# LazuriteBLE_rev1.net
KiCad netlist of a schematic drawn in EAGLE
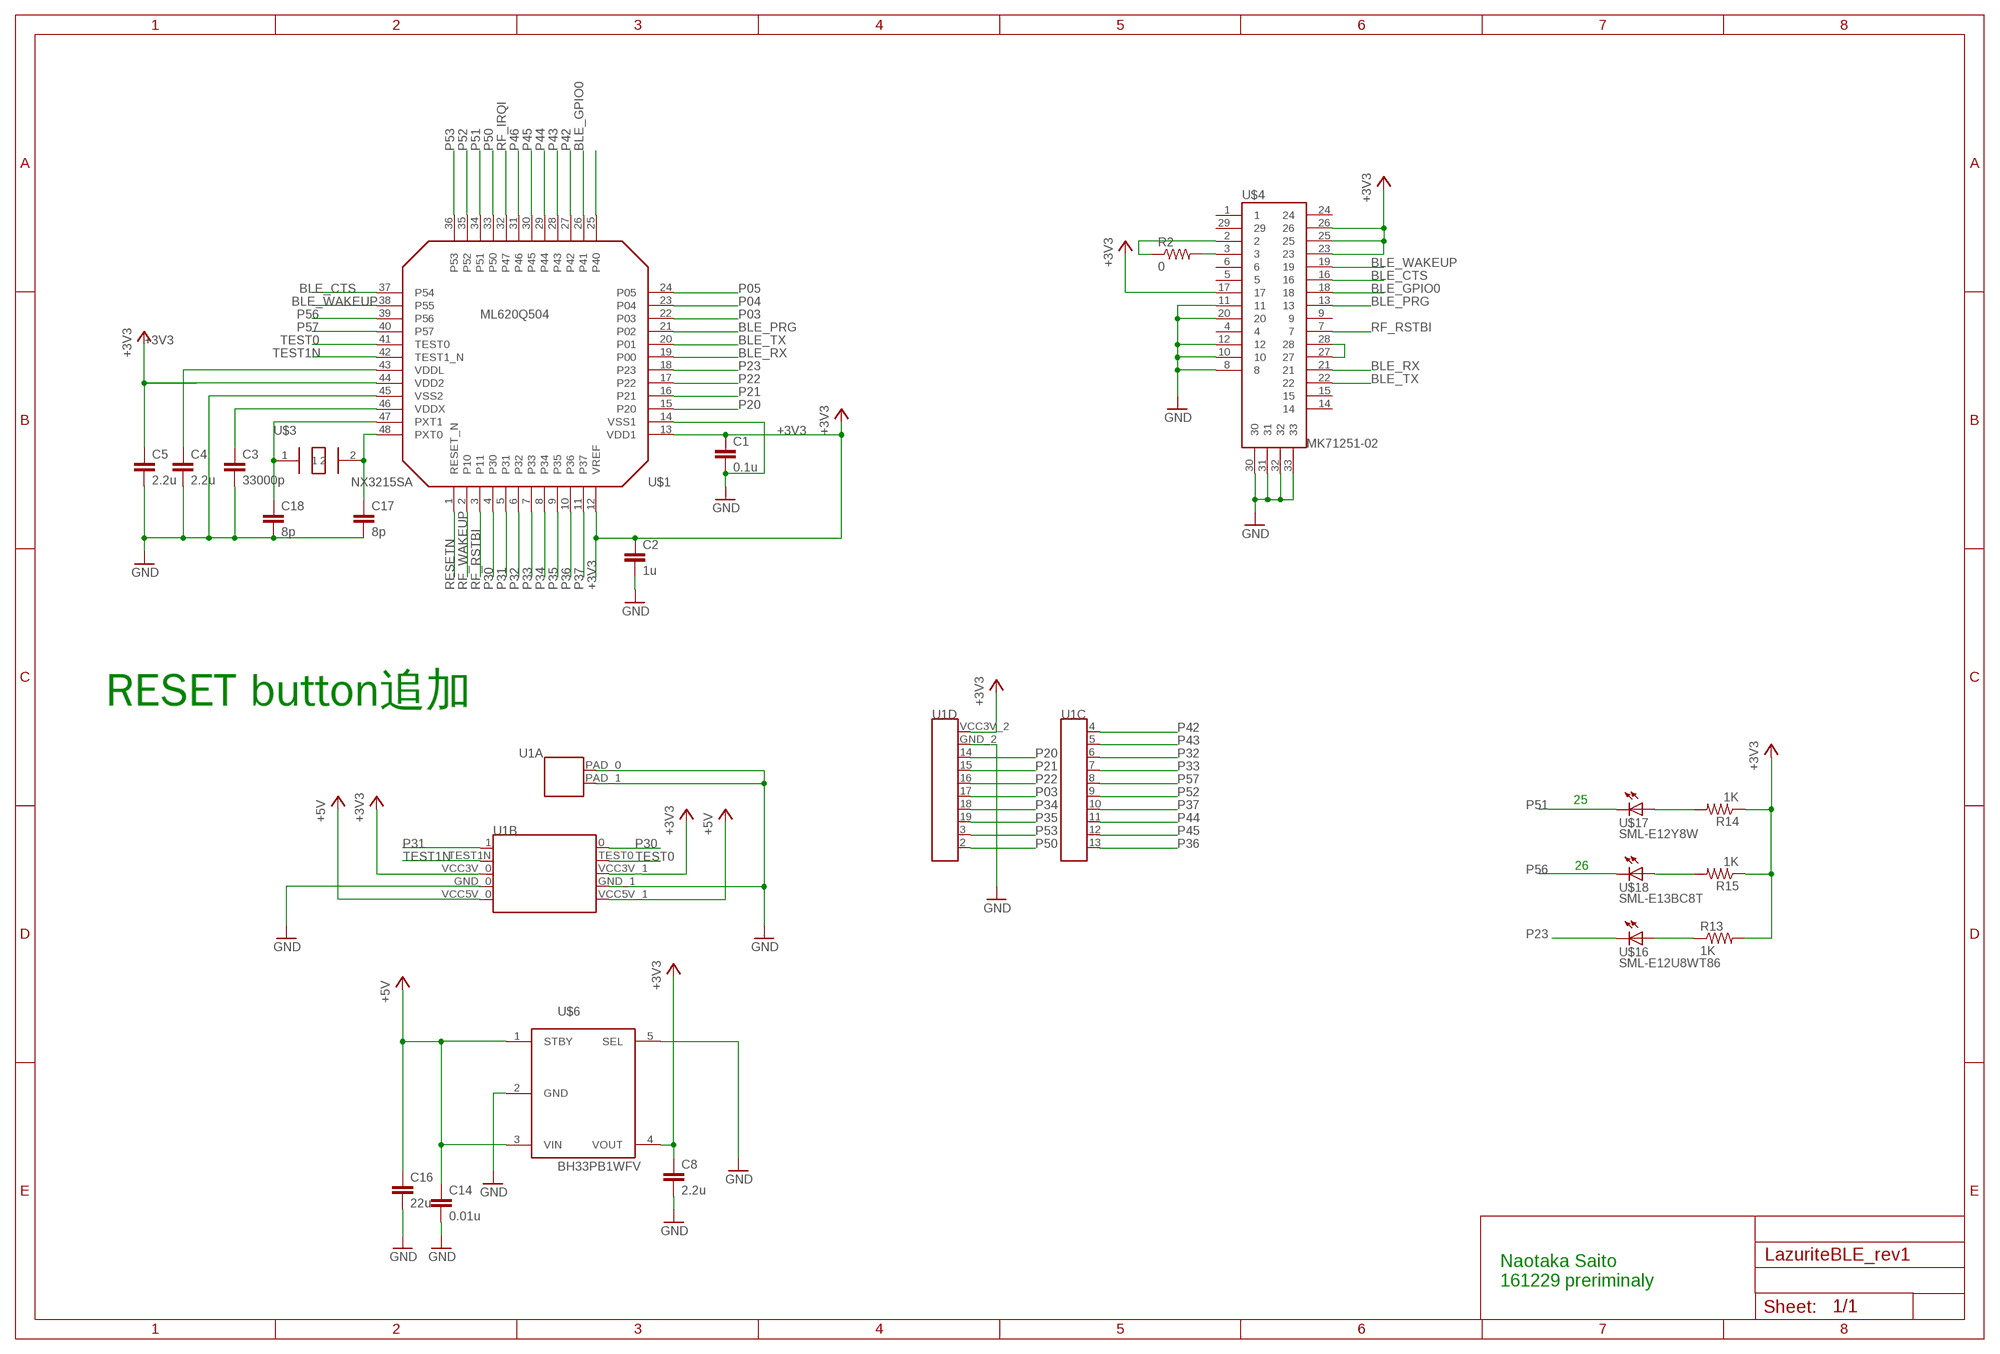
[diagram p0: schematic, sheet 1]

(export (version "E")
  (design (tool "Eeschema 10.0.6"))
  (components
    (comp (ref "C1")
      (value "0.1u")
      (footprint "eagle-import:C0402")
      (libsource (lib "eagle-import") (part "C-EUC0402"))
    )
    (comp (ref "C2")
      (value "1u")
      (footprint "eagle-import:C0402")
      (libsource (lib "eagle-import") (part "C-EUC0402"))
    )
    (comp (ref "C3")
      (value "33000p")
      (footprint "eagle-import:C0402")
      (libsource (lib "eagle-import") (part "C-EUC0402"))
    )
    (comp (ref "C4")
      (value "2.2u")
      (footprint "eagle-import:C0402")
      (libsource (lib "eagle-import") (part "C-EUC0402"))
    )
    (comp (ref "C5")
      (value "2.2u")
      (footprint "eagle-import:C0402")
      (libsource (lib "eagle-import") (part "C-EUC0402"))
    )
    (comp (ref "C8")
      (value "2.2u")
      (footprint "eagle-import:C0402")
      (libsource (lib "eagle-import") (part "C-EUC0402"))
    )
    (comp (ref "C14")
      (value "0.01u")
      (footprint "eagle-import:C0402")
      (libsource (lib "eagle-import") (part "C-EUC0402"))
    )
    (comp (ref "C16")
      (value "22u")
      (footprint "eagle-import:C1206")
      (libsource (lib "eagle-import") (part "C-EUC1206"))
    )
    (comp (ref "C17")
      (value "8p")
      (footprint "eagle-import:C0402")
      (libsource (lib "eagle-import") (part "C-EUC0402"))
    )
    (comp (ref "C18")
      (value "8p")
      (footprint "eagle-import:C0402")
      (libsource (lib "eagle-import") (part "C-EUC0402"))
    )
    (comp (ref "R2")
      (value "0")
      (footprint "eagle-import:R0402")
      (libsource (lib "eagle-import") (part "R-US_R0402"))
    )
    (comp (ref "R13")
      (value "1K")
      (footprint "eagle-import:R0402")
      (libsource (lib "eagle-import") (part "R-US_R0402"))
    )
    (comp (ref "R14")
      (value "1K")
      (footprint "eagle-import:R0402")
      (libsource (lib "eagle-import") (part "R-US_R0402"))
    )
    (comp (ref "R15")
      (value "1K")
      (footprint "eagle-import:R0402")
      (libsource (lib "eagle-import") (part "R-US_R0402"))
    )
    (comp (ref "U$1")
      (value "ML620Q504")
      (footprint "eagle-import:ML620Q504")
      (libsource (lib "eagle-import") (part "ML620Q504"))
    )
    (comp (ref "U$3")
      (value "NX3215SA")
      (footprint "eagle-import:NX3215SA-32,768K-SFD-MUA-14")
      (libsource (lib "eagle-import") (part "NX3215SA"))
    )
    (comp (ref "U$4")
      (value "MK71251-02")
      (footprint "eagle-import:MK71251-02")
      (libsource (lib "eagle-import") (part "MK71251-02"))
    )
    (comp (ref "U$6")
      (value "BH33PB1WFV")
      (footprint "eagle-import:HVSOF5")
      (libsource (lib "eagle-import") (part "BHXXPB1WFV"))
    )
    (comp (ref "U$16")
      (value "SML-E12U8WT86")
      (footprint "eagle-import:SML-E1X")
      (libsource (lib "eagle-import") (part "SML-E1X"))
    )
    (comp (ref "U$17")
      (value "SML-E12Y8W")
      (footprint "eagle-import:SML-E1X")
      (libsource (lib "eagle-import") (part "SML-E1X"))
    )
    (comp (ref "U$18")
      (value "SML-E13BC8T")
      (footprint "eagle-import:SML-E1X")
      (libsource (lib "eagle-import") (part "SML-E1X"))
    )
    (comp (ref "U1")
      (value "LAZURITE920J")
      (footprint "eagle-import:LAZURITE920J2")
      (libsource (lib "eagle-import") (part "LAZURITE920J"))
    )
  )
  (nets
    (net (code "1") (name "+3V3") (class "Default")
      (node (ref "C1") (pin "1") (pinfunction "1_1") (pintype "passive"))
      (node (ref "C2") (pin "1") (pinfunction "1_1") (pintype "passive"))
      (node (ref "C5") (pin "1") (pinfunction "1_1") (pintype "passive"))
      (node (ref "C8") (pin "1") (pinfunction "1_1") (pintype "passive"))
      (node (ref "R13") (pin "2") (pinfunction "2_2") (pintype "passive"))
      (node (ref "R14") (pin "1") (pinfunction "1_1") (pintype "passive"))
      (node (ref "R15") (pin "1") (pinfunction "1_1") (pintype "passive"))
      (node (ref "U$1") (pin "12") (pinfunction "VREF_12") (pintype "bidirectional"))
      (node (ref "U$1") (pin "13") (pinfunction "VDD1_13") (pintype "bidirectional"))
      (node (ref "U$1") (pin "44") (pinfunction "VDD2_44") (pintype "bidirectional"))
      (node (ref "U$4") (pin "17") (pinfunction "17_17") (pintype "power_in"))
      (node (ref "U$4") (pin "23") (pinfunction "23_23") (pintype "bidirectional"))
      (node (ref "U$4") (pin "25") (pinfunction "25_25") (pintype "bidirectional"))
      (node (ref "U$4") (pin "26") (pinfunction "26_26") (pintype "bidirectional"))
      (node (ref "U$6") (pin "4") (pinfunction "VOUT_4") (pintype "bidirectional"))
      (node (ref "U1") (pin "VCC3V_0") (pinfunction "VCC3V_0_VCC3V_0") (pintype "passive"))
      (node (ref "U1") (pin "VCC3V_1") (pinfunction "VCC3V_1_VCC3V_1") (pintype "passive"))
      (node (ref "U1") (pin "VCC3V_2") (pinfunction "VCC3V_2_VCC3V_2") (pintype "passive"))
    )
    (net (code "2") (name "+5V") (class "Default")
      (node (ref "C14") (pin "1") (pinfunction "1_1") (pintype "passive"))
      (node (ref "C16") (pin "1") (pinfunction "1_1") (pintype "passive"))
      (node (ref "U$6") (pin "1") (pinfunction "STBY_1") (pintype "bidirectional"))
      (node (ref "U$6") (pin "3") (pinfunction "VIN_3") (pintype "bidirectional"))
      (node (ref "U1") (pin "VCC5V_0") (pinfunction "VCC5V_0_VCC5V_0") (pintype "passive"))
      (node (ref "U1") (pin "VCC5V_1") (pinfunction "VCC5V_1_VCC5V_1") (pintype "passive"))
    )
    (net (code "3") (name "/BLE_CTS") (class "Default")
      (node (ref "U$1") (pin "37") (pinfunction "P54_37") (pintype "bidirectional"))
      (node (ref "U$4") (pin "16") (pinfunction "16_16") (pintype "bidirectional"))
    )
    (net (code "4") (name "/BLE_GPIO0") (class "Default")
      (node (ref "U$1") (pin "26") (pinfunction "P41_26") (pintype "bidirectional"))
      (node (ref "U$4") (pin "18") (pinfunction "18_18") (pintype "bidirectional"))
    )
    (net (code "5") (name "/BLE_PRG") (class "Default")
      (node (ref "U$1") (pin "21") (pinfunction "P02_21") (pintype "bidirectional"))
      (node (ref "U$4") (pin "13") (pinfunction "13_13") (pintype "bidirectional"))
    )
    (net (code "6") (name "/BLE_RX") (class "Default")
      (node (ref "U$1") (pin "19") (pinfunction "P00_19") (pintype "bidirectional"))
      (node (ref "U$4") (pin "21") (pinfunction "21_21") (pintype "bidirectional"))
    )
    (net (code "7") (name "/BLE_TX") (class "Default")
      (node (ref "U$1") (pin "20") (pinfunction "P01_20") (pintype "bidirectional"))
      (node (ref "U$4") (pin "22") (pinfunction "22_22") (pintype "bidirectional"))
    )
    (net (code "8") (name "/BLE_WAKEUP") (class "Default")
      (node (ref "U$1") (pin "38") (pinfunction "P55_38") (pintype "bidirectional"))
      (node (ref "U$4") (pin "19") (pinfunction "19_19") (pintype "input"))
    )
    (net (code "9") (name "/P03") (class "Default")
      (node (ref "U$1") (pin "22") (pinfunction "P03_22") (pintype "bidirectional"))
      (node (ref "U1") (pin "17") (pinfunction "17_17") (pintype "passive"))
    )
    (net (code "10") (name "/P04") (class "Default")
      (node (ref "U$1") (pin "23") (pinfunction "P04_23") (pintype "bidirectional"))
    )
    (net (code "11") (name "/P05") (class "Default")
      (node (ref "U$1") (pin "24") (pinfunction "P05_24") (pintype "bidirectional"))
    )
    (net (code "12") (name "/P20") (class "Default")
      (node (ref "U$1") (pin "15") (pinfunction "P20_15") (pintype "bidirectional"))
      (node (ref "U1") (pin "14") (pinfunction "14_14") (pintype "passive"))
    )
    (net (code "13") (name "/P21") (class "Default")
      (node (ref "U$1") (pin "16") (pinfunction "P21_16") (pintype "bidirectional"))
      (node (ref "U1") (pin "15") (pinfunction "15_15") (pintype "passive"))
    )
    (net (code "14") (name "/P22") (class "Default")
      (node (ref "U$1") (pin "17") (pinfunction "P22_17") (pintype "bidirectional"))
      (node (ref "U1") (pin "16") (pinfunction "16_16") (pintype "passive"))
    )
    (net (code "15") (name "/P23") (class "Default")
      (node (ref "U$1") (pin "18") (pinfunction "P23_18") (pintype "bidirectional"))
      (node (ref "U$16") (pin "C") (pinfunction "C_C") (pintype "passive"))
    )
    (net (code "16") (name "/P30") (class "Default")
      (node (ref "U$1") (pin "4") (pinfunction "P30_4") (pintype "bidirectional"))
      (node (ref "U1") (pin "0") (pinfunction "0_0") (pintype "passive"))
    )
    (net (code "17") (name "/P31") (class "Default")
      (node (ref "U$1") (pin "5") (pinfunction "P31_5") (pintype "bidirectional"))
      (node (ref "U1") (pin "1") (pinfunction "1_1") (pintype "passive"))
    )
    (net (code "18") (name "/P32") (class "Default")
      (node (ref "U$1") (pin "6") (pinfunction "P32_6") (pintype "bidirectional"))
      (node (ref "U1") (pin "6") (pinfunction "6_6") (pintype "passive"))
    )
    (net (code "19") (name "/P33") (class "Default")
      (node (ref "U$1") (pin "7") (pinfunction "P33_7") (pintype "bidirectional"))
      (node (ref "U1") (pin "7") (pinfunction "7_7") (pintype "passive"))
    )
    (net (code "20") (name "/P34") (class "Default")
      (node (ref "U$1") (pin "8") (pinfunction "P34_8") (pintype "bidirectional"))
      (node (ref "U1") (pin "18") (pinfunction "18_18") (pintype "passive"))
    )
    (net (code "21") (name "/P35") (class "Default")
      (node (ref "U$1") (pin "9") (pinfunction "P35_9") (pintype "bidirectional"))
      (node (ref "U1") (pin "19") (pinfunction "19_19") (pintype "passive"))
    )
    (net (code "22") (name "/P36") (class "Default")
      (node (ref "U$1") (pin "10") (pinfunction "P36_10") (pintype "bidirectional"))
      (node (ref "U1") (pin "13") (pinfunction "13_13") (pintype "passive"))
    )
    (net (code "23") (name "/P37") (class "Default")
      (node (ref "U$1") (pin "11") (pinfunction "P37_11") (pintype "bidirectional"))
      (node (ref "U1") (pin "10") (pinfunction "10_10") (pintype "passive"))
    )
    (net (code "24") (name "/P42") (class "Default")
      (node (ref "U$1") (pin "27") (pinfunction "P42_27") (pintype "bidirectional"))
      (node (ref "U1") (pin "4") (pinfunction "4_4") (pintype "passive"))
    )
    (net (code "25") (name "/P43") (class "Default")
      (node (ref "U$1") (pin "28") (pinfunction "P43_28") (pintype "bidirectional"))
      (node (ref "U1") (pin "5") (pinfunction "5_5") (pintype "passive"))
    )
    (net (code "26") (name "/P44") (class "Default")
      (node (ref "U$1") (pin "29") (pinfunction "P44_29") (pintype "bidirectional"))
      (node (ref "U1") (pin "11") (pinfunction "11_11") (pintype "passive"))
    )
    (net (code "27") (name "/P45") (class "Default")
      (node (ref "U$1") (pin "30") (pinfunction "P45_30") (pintype "bidirectional"))
      (node (ref "U1") (pin "12") (pinfunction "12_12") (pintype "passive"))
    )
    (net (code "28") (name "/P46") (class "Default")
      (node (ref "U$1") (pin "31") (pinfunction "P46_31") (pintype "bidirectional"))
    )
    (net (code "29") (name "/P50") (class "Default")
      (node (ref "U$1") (pin "33") (pinfunction "P50_33") (pintype "bidirectional"))
      (node (ref "U1") (pin "2") (pinfunction "2_2") (pintype "passive"))
    )
    (net (code "30") (name "/P51") (class "Default")
      (node (ref "U$1") (pin "34") (pinfunction "P51_34") (pintype "bidirectional"))
      (node (ref "U$17") (pin "C") (pinfunction "C_C") (pintype "passive"))
    )
    (net (code "31") (name "/P52") (class "Default")
      (node (ref "U$1") (pin "35") (pinfunction "P52_35") (pintype "bidirectional"))
      (node (ref "U1") (pin "9") (pinfunction "9_9") (pintype "passive"))
    )
    (net (code "32") (name "/P53") (class "Default")
      (node (ref "U$1") (pin "36") (pinfunction "P53_36") (pintype "bidirectional"))
      (node (ref "U1") (pin "3") (pinfunction "3_3") (pintype "passive"))
    )
    (net (code "33") (name "/P56") (class "Default")
      (node (ref "U$1") (pin "39") (pinfunction "P56_39") (pintype "bidirectional"))
      (node (ref "U$18") (pin "C") (pinfunction "C_C") (pintype "passive"))
    )
    (net (code "34") (name "/P57") (class "Default")
      (node (ref "U$1") (pin "40") (pinfunction "P57_40") (pintype "bidirectional"))
      (node (ref "U1") (pin "8") (pinfunction "8_8") (pintype "passive"))
    )
    (net (code "35") (name "/RESETN") (class "Default")
      (node (ref "U$1") (pin "1") (pinfunction "RESET_N_1") (pintype "bidirectional"))
    )
    (net (code "36") (name "/RF_IRQI") (class "Default")
      (node (ref "U$1") (pin "32") (pinfunction "P47_32") (pintype "bidirectional"))
    )
    (net (code "37") (name "/RF_RSTBI") (class "Default")
      (node (ref "U$1") (pin "3") (pinfunction "P11_3") (pintype "bidirectional"))
      (node (ref "U$4") (pin "7") (pinfunction "7_7") (pintype "input"))
    )
    (net (code "38") (name "/RF_WAKEUP") (class "Default")
      (node (ref "U$1") (pin "2") (pinfunction "P10_2") (pintype "bidirectional"))
    )
    (net (code "39") (name "/TEST0") (class "Default")
      (node (ref "U$1") (pin "41") (pinfunction "TEST0_41") (pintype "bidirectional"))
      (node (ref "U1") (pin "TEST0") (pinfunction "TEST0_TEST0") (pintype "passive"))
    )
    (net (code "40") (name "/TEST1N") (class "Default")
      (node (ref "U$1") (pin "42") (pinfunction "TEST1_N_42") (pintype "bidirectional"))
      (node (ref "U1") (pin "TEST1N") (pinfunction "TEST1N_TEST1N") (pintype "passive"))
    )
    (net (code "41") (name "GND") (class "Default")
      (node (ref "C1") (pin "2") (pinfunction "2_2") (pintype "passive"))
      (node (ref "C14") (pin "2") (pinfunction "2_2") (pintype "passive"))
      (node (ref "C16") (pin "2") (pinfunction "2_2") (pintype "passive"))
      (node (ref "C17") (pin "2") (pinfunction "2_2") (pintype "passive"))
      (node (ref "C18") (pin "2") (pinfunction "2_2") (pintype "passive"))
      (node (ref "C2") (pin "2") (pinfunction "2_2") (pintype "passive"))
      (node (ref "C3") (pin "2") (pinfunction "2_2") (pintype "passive"))
      (node (ref "C4") (pin "2") (pinfunction "2_2") (pintype "passive"))
      (node (ref "C5") (pin "2") (pinfunction "2_2") (pintype "passive"))
      (node (ref "C8") (pin "2") (pinfunction "2_2") (pintype "passive"))
      (node (ref "U$1") (pin "14") (pinfunction "VSS1_14") (pintype "bidirectional"))
      (node (ref "U$1") (pin "45") (pinfunction "VSS2_45") (pintype "bidirectional"))
      (node (ref "U$4") (pin "10") (pinfunction "10_10") (pintype "input"))
      (node (ref "U$4") (pin "11") (pinfunction "11_11") (pintype "bidirectional"))
      (node (ref "U$4") (pin "12") (pinfunction "12_12") (pintype "input"))
      (node (ref "U$4") (pin "20") (pinfunction "20_20") (pintype "bidirectional"))
      (node (ref "U$4") (pin "30") (pinfunction "30_30") (pintype "power_in"))
      (node (ref "U$4") (pin "31") (pinfunction "31_31") (pintype "power_in"))
      (node (ref "U$4") (pin "32") (pinfunction "32_32") (pintype "power_in"))
      (node (ref "U$4") (pin "33") (pinfunction "33_33") (pintype "power_in"))
      (node (ref "U$4") (pin "8") (pinfunction "8_8") (pintype "input"))
      (node (ref "U$6") (pin "2") (pinfunction "GND_2") (pintype "bidirectional"))
      (node (ref "U$6") (pin "5") (pinfunction "SEL_5") (pintype "bidirectional"))
      (node (ref "U1") (pin "GND_0") (pinfunction "GND_0_GND_0") (pintype "passive"))
      (node (ref "U1") (pin "GND_1") (pinfunction "GND_1_GND_1") (pintype "passive"))
      (node (ref "U1") (pin "GND_2") (pinfunction "GND_2_GND_2") (pintype "passive"))
      (node (ref "U1") (pin "PAD_0") (pinfunction "PAD_0_PAD_0") (pintype "passive"))
      (node (ref "U1") (pin "PAD_1") (pinfunction "PAD_1_PAD_1") (pintype "passive"))
    )
    (net (code "42") (name "Net-(R2-Pad1)") (class "Default")
      (node (ref "R2") (pin "1") (pinfunction "1_1") (pintype "passive"))
      (node (ref "U$4") (pin "2") (pinfunction "2_2") (pintype "input"))
    )
    (net (code "43") (name "Net-(R2-Pad2)") (class "Default")
      (node (ref "R2") (pin "2") (pinfunction "2_2") (pintype "passive"))
      (node (ref "U$4") (pin "3") (pinfunction "3_3") (pintype "bidirectional"))
    )
    (net (code "44") (name "Net-(R13-Pad1)") (class "Default")
      (node (ref "R13") (pin "1") (pinfunction "1_1") (pintype "passive"))
      (node (ref "U$16") (pin "A") (pinfunction "A_A") (pintype "passive"))
    )
    (net (code "45") (name "Net-(R14-Pad2)") (class "Default")
      (node (ref "R14") (pin "2") (pinfunction "2_2") (pintype "passive"))
      (node (ref "U$17") (pin "A") (pinfunction "A_A") (pintype "passive"))
    )
    (net (code "46") (name "Net-(R15-Pad2)") (class "Default")
      (node (ref "R15") (pin "2") (pinfunction "2_2") (pintype "passive"))
      (node (ref "U$18") (pin "A") (pinfunction "A_A") (pintype "passive"))
    )
    (net (code "47") (name "Net-(U$1-PXT0)") (class "Default")
      (node (ref "C17") (pin "1") (pinfunction "1_1") (pintype "passive"))
      (node (ref "U$1") (pin "48") (pinfunction "PXT0_48") (pintype "bidirectional"))
      (node (ref "U$3") (pin "2") (pinfunction "2_2") (pintype "bidirectional"))
    )
    (net (code "48") (name "Net-(U$1-PXT1)") (class "Default")
      (node (ref "C18") (pin "1") (pinfunction "1_1") (pintype "passive"))
      (node (ref "U$1") (pin "47") (pinfunction "PXT1_47") (pintype "bidirectional"))
      (node (ref "U$3") (pin "1") (pinfunction "1_1") (pintype "bidirectional"))
    )
    (net (code "49") (name "Net-(U$1-VDDL)") (class "Default")
      (node (ref "C4") (pin "1") (pinfunction "1_1") (pintype "passive"))
      (node (ref "U$1") (pin "43") (pinfunction "VDDL_43") (pintype "bidirectional"))
    )
    (net (code "50") (name "Net-(U$1-VDDX)") (class "Default")
      (node (ref "C3") (pin "1") (pinfunction "1_1") (pintype "passive"))
      (node (ref "U$1") (pin "46") (pinfunction "VDDX_46") (pintype "bidirectional"))
    )
    (net (code "51") (name "Net-(U$4-Pad27)") (class "Default")
      (node (ref "U$4") (pin "27") (pinfunction "27_27") (pintype "bidirectional"))
      (node (ref "U$4") (pin "28") (pinfunction "28_28") (pintype "bidirectional"))
    )
    (net (code "52") (name "unconnected-(U$1-P40-Pad25)") (class "Default")
      (node (ref "U$1") (pin "25") (pinfunction "P40_25") (pintype "bidirectional"))
    )
    (net (code "53") (name "unconnected-(U$4-Pad1)") (class "Default")
      (node (ref "U$4") (pin "1") (pinfunction "1_1") (pintype "no_connect"))
    )
    (net (code "54") (name "unconnected-(U$4-Pad4)") (class "Default")
      (node (ref "U$4") (pin "4") (pinfunction "4_4") (pintype "bidirectional"))
    )
    (net (code "55") (name "unconnected-(U$4-Pad5)") (class "Default")
      (node (ref "U$4") (pin "5") (pinfunction "5_5") (pintype "bidirectional"))
    )
    (net (code "56") (name "unconnected-(U$4-Pad6)") (class "Default")
      (node (ref "U$4") (pin "6") (pinfunction "6_6") (pintype "bidirectional"))
    )
    (net (code "57") (name "unconnected-(U$4-Pad9)") (class "Default")
      (node (ref "U$4") (pin "9") (pinfunction "9_9") (pintype "bidirectional"))
    )
    (net (code "58") (name "unconnected-(U$4-Pad14)") (class "Default")
      (node (ref "U$4") (pin "14") (pinfunction "14_14") (pintype "bidirectional"))
    )
    (net (code "59") (name "unconnected-(U$4-Pad15)") (class "Default")
      (node (ref "U$4") (pin "15") (pinfunction "15_15") (pintype "bidirectional"))
    )
    (net (code "60") (name "unconnected-(U$4-Pad24)") (class "Default")
      (node (ref "U$4") (pin "24") (pinfunction "24_24") (pintype "bidirectional"))
    )
    (net (code "61") (name "unconnected-(U$4-Pad29)") (class "Default")
      (node (ref "U$4") (pin "29") (pinfunction "29_29") (pintype "no_connect"))
    )
  )
)
